# GNSS_SUPPORT.net
KiCad netlist of a schematic drawn in Altium Designer
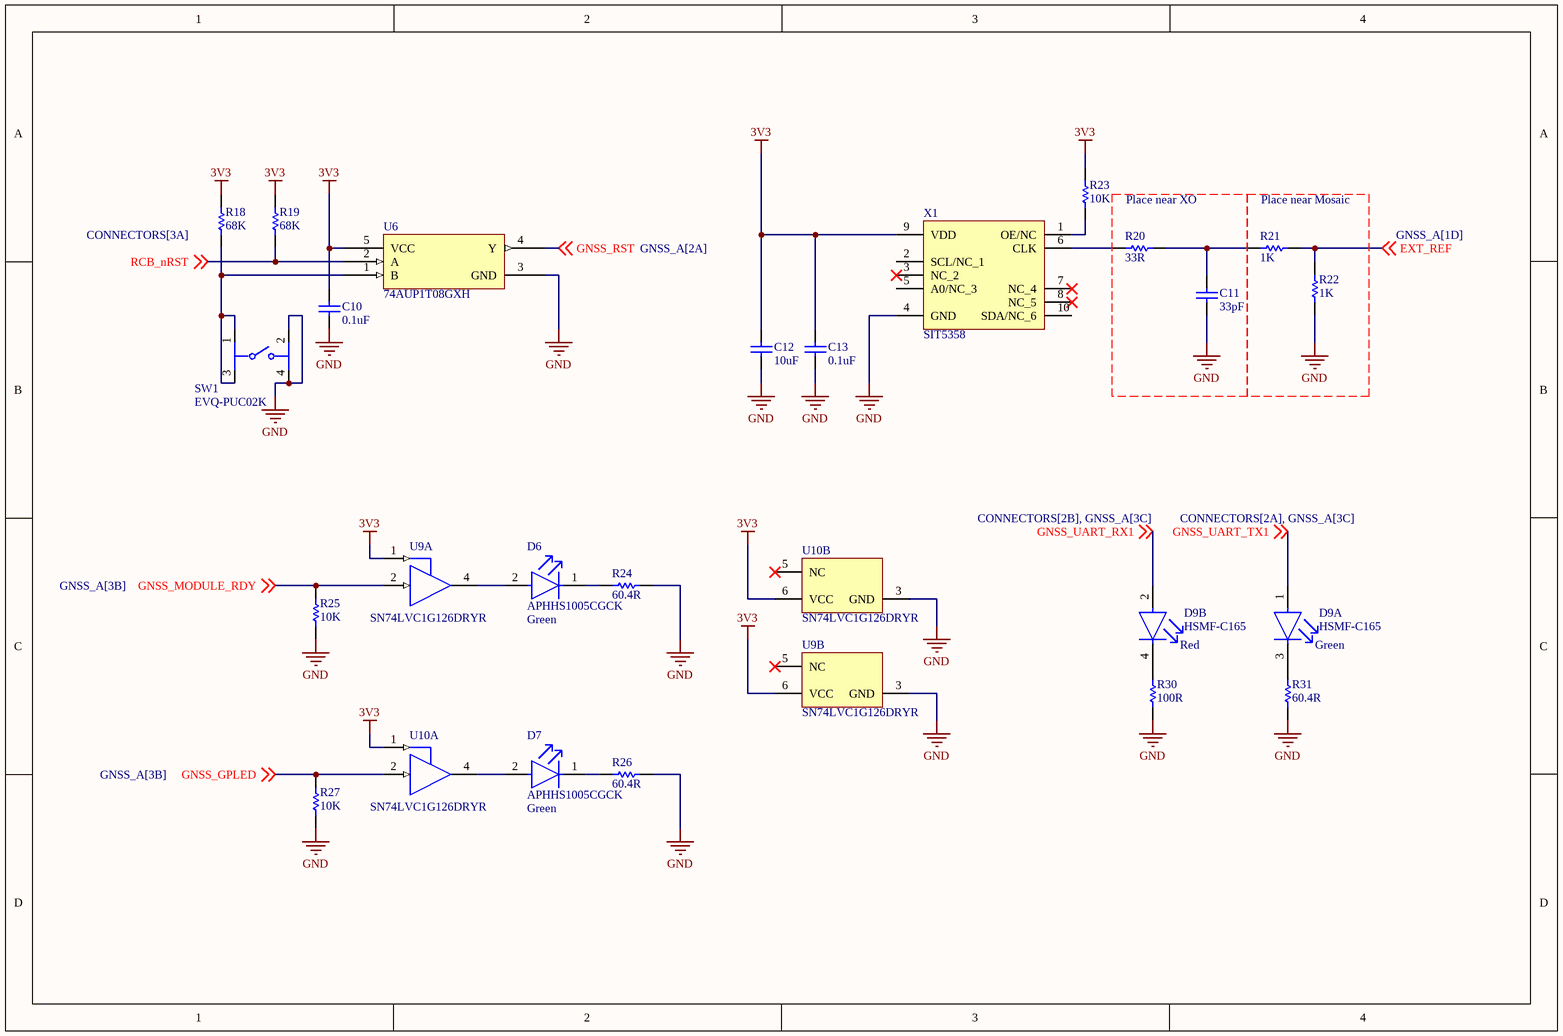
[diagram p0: GNSS_SUPPORT.SchDoc]

(export (version "E")
  (design (tool "Eeschema 10.0.6"))
  (components
    (comp (ref "C10")
      (value "0.1uF")
      (footprint "CAPC1005X56X25LL10T15")
      (fields
        (field (name "MANUFACTURER") "AVX Interconnect / Elco")
        (field (name "PART NUMBER") "04026D104KAT2A")
      )
      (libsource (lib "Altium Content Vault") (part "CAP"))
    )
    (comp (ref "C11")
      (value "33pF")
      (footprint "CAPC1005X55X25ML05T10")
      (fields (field (name "PART NUMBER") "GRM1555C1H330JZ01D") (field (name "MANUFACTURER") "Murata"))
      (libsource (lib "Altium Content Vault") (part "CAP"))
    )
    (comp (ref "C12")
      (value "10uF")
      (footprint "CAPC1005X70X10LL05")
      (description "Chip Capacitor, 10 uF, +/- 20%, -55 to 85 degC, 0402 (1005 Metric), RoHS, Tape and Reel")
      (fields
        (field (name "PCN PART NUMBER") "MLCCPartNumberChange30/Nov/2012")
        (field (name "TOLERANCE") "±20%")
      )
      (libsource (lib "Altium Content Vault") (part "CAP-NP-2"))
    )
    (comp (ref "C13")
      (value "0.1uF")
      (footprint "CAPC1005X56X25LL10T15")
      (fields
        (field (name "MANUFACTURER") "AVX Interconnect / Elco")
        (field (name "PART NUMBER") "04026D104KAT2A")
      )
      (libsource (lib "Altium Content Vault") (part "CAP"))
    )
    (comp (ref "D6")
      (value "APHHS1005CGCK")
      (footprint "FP-APHHS1005CGCK-MFG")
      (description "LED GREEN CLEAR CHIP SMD")
      (fields (field (name "COLOR") "Green"))
      (libsource (lib "Altium Content Vault") (part "8706943c75ba83719d021d2fdc84c58"))
    )
    (comp (ref "D7")
      (value "APHHS1005CGCK")
      (footprint "FP-APHHS1005CGCK-MFG")
      (description "LED GREEN CLEAR CHIP SMD")
      (fields (field (name "COLOR") "Green"))
      (libsource (lib "Altium Content Vault") (part "8706943c75ba83719d021d2fdc84c58"))
    )
    (comp (ref "D9")
      (value "HSMF-C165")
      (footprint "FP-HSMF-C165-MFG")
      (description "LED GREEN/RED DIFFUSED 0603 SMD")
      (libsource (lib "Altium Content Vault") (part "7c1fe340d8ce6b5db8c50b7ec3493de"))
    )
    (comp (ref "R18")
      (value "68K")
      (footprint "RESC1005X40X25LL10T10")
      (fields (field (name "PART NUMBER") "ERA2AEB683X") (field (name "MANUFACTURER") "Panasonic"))
      (libsource (lib "Altium Content Vault") (part "RES"))
    )
    (comp (ref "R19")
      (value "68K")
      (footprint "RESC1005X40X25LL10T10")
      (fields (field (name "PART NUMBER") "ERA2AEB683X") (field (name "MANUFACTURER") "Panasonic"))
      (libsource (lib "Altium Content Vault") (part "RES"))
    )
    (comp (ref "R20")
      (value "33R")
      (footprint "RESC1005X40X25LL05T10")
      (fields (field (name "PART NUMBER") "RC0402FR-0733RL") (field (name "MANUFACTURER") "Yageo / Phycomp"))
      (libsource (lib "Altium Content Vault") (part "RES"))
    )
    (comp (ref "R21")
      (value "1K")
      (footprint "RESC1005X40X25LL05T10")
      (fields (field (name "PART NUMBER") "CRCW04021K00FKEDHP") (field (name "MANUFACTURER") "Vishay Dale"))
      (libsource (lib "Altium Content Vault") (part "RES"))
    )
    (comp (ref "R22")
      (value "1K")
      (footprint "RESC1005X40X25LL05T10")
      (fields (field (name "PART NUMBER") "CRCW04021K00FKEDHP") (field (name "MANUFACTURER") "Vishay Dale"))
      (libsource (lib "Altium Content Vault") (part "RES"))
    )
    (comp (ref "R23")
      (value "10K")
      (footprint "RESC1005X40X25ML05T10")
      (fields (field (name "PART NUMBER") "CRCW040210K0FKEDHP") (field (name "MANUFACTURER") "Vishay Dale"))
      (libsource (lib "Altium Content Vault") (part "RES"))
    )
    (comp (ref "R24")
      (value "60.4R")
      (footprint "RESC1005X40X25ML05T05")
      (fields (field (name "PART NUMBER") "ERJ-2RKF6040X") (field (name "MANUFACTURER") "Panasonic"))
      (libsource (lib "Altium Content Vault") (part "RES"))
    )
    (comp (ref "R25")
      (value "10K")
      (footprint "RESC1005X40X25ML05T10")
      (fields (field (name "PART NUMBER") "CRCW040210K0FKEDHP") (field (name "MANUFACTURER") "Vishay Dale"))
      (libsource (lib "Altium Content Vault") (part "RES"))
    )
    (comp (ref "R26")
      (value "60.4R")
      (footprint "RESC1005X40X25ML05T05")
      (fields (field (name "PART NUMBER") "ERJ-2RKF6040X") (field (name "MANUFACTURER") "Panasonic"))
      (libsource (lib "Altium Content Vault") (part "RES"))
    )
    (comp (ref "R27")
      (value "10K")
      (footprint "RESC1005X40X25ML05T10")
      (fields (field (name "PART NUMBER") "CRCW040210K0FKEDHP") (field (name "MANUFACTURER") "Vishay Dale"))
      (libsource (lib "Altium Content Vault") (part "RES"))
    )
    (comp (ref "R30")
      (value "100R")
      (footprint "RESC1005X40X25LL05T05")
      (description "Chip Resistor, 100 Ohm, +/- 1%, 100 mW, -55 to 155 degC, 0402 (1005 Metric), RoHS, Tape and Reel")
      (fields (field (name "MANUFACTURER") "Basic Passives") (field (name "TOLERANCE") "1%"))
      (libsource (lib "Altium Content Vault") (part "RES-2"))
    )
    (comp (ref "R31")
      (value "60.4R")
      (footprint "RESC1005X40X25ML05T05")
      (fields (field (name "PART NUMBER") "ERJ-2RKF6040X") (field (name "MANUFACTURER") "Panasonic"))
      (libsource (lib "Altium Content Vault") (part "RES"))
    )
    (comp (ref "SW1")
      (value "EVQ-PUC02K")
      (footprint "FP-EVQ-PUC02K-MFG")
      (description "SWITCH TACTILE SPST-NO 0.05A 12V")
      (libsource (lib "Altium Content Vault") (part "cb67941ecbda1860b707deecc235d4d"))
    )
    (comp (ref "U6")
      (value "74AUP1T08GXH")
      (footprint "X2SON5_SOT1226_NEX")
      (description "No Description Available")
      (fields (field (name "COPYRIGHT") "Copyright (C) 2023 Ultra Librarian. All rights reserved."))
      (libsource (lib "74AUP1T08GXH") (part "74AUP1T08GXH"))
    )
    (comp (ref "U9")
      (value "SN74LVC1G126DRYR")
      (footprint "DRY0006A_V")
      (description "Single Bus Buffer Gate With 3-State Outputs, DRY0006A, LARGE T&R")
      (fields
        (field (name "MANUFACTURER") "Texas Instruments")
        (field (name "GENERIC PART NUMBER") "SN74LVC1G126")
      )
      (libsource (lib "Altium Content Vault") (part "TI-SN74XXX1G126-6"))
    )
    (comp (ref "U10")
      (value "SN74LVC1G126DRYR")
      (footprint "DRY0006A_V")
      (description "Single Bus Buffer Gate With 3-State Outputs, DRY0006A, LARGE T&R")
      (fields
        (field (name "MANUFACTURER") "Texas Instruments")
        (field (name "GENERIC PART NUMBER") "SN74LVC1G126")
      )
      (libsource (lib "Altium Content Vault") (part "TI-SN74XXX1G126-6"))
    )
    (comp (ref "X1")
      (value "SIT5358")
      (footprint "SIT5358")
      (description "1 to 60 MHz, ±50 ppb Super-TCXO")
      (fields (field (name "MANUFACTURER_PART_NUMBER") "SIT5358AN-FR-33N0-10.000000"))
      (libsource (lib "SIT5358") (part "SIT5358"))
    )
  )
  (nets
    (net (code "1") (name "3V3") (class "Default")
      (node (ref "C10") (pin "2") (pinfunction "2_2") (pintype "passive"))
      (node (ref "C12") (pin "2") (pinfunction "2_2") (pintype "passive"))
      (node (ref "C13") (pin "2") (pinfunction "2_2") (pintype "passive"))
      (node (ref "R18") (pin "2") (pinfunction "2_2") (pintype "passive"))
      (node (ref "R19") (pin "2") (pinfunction "2_2") (pintype "passive"))
      (node (ref "R23") (pin "2") (pinfunction "2_2") (pintype "passive"))
      (node (ref "U10") (pin "1") (pinfunction "OE_1") (pintype "input"))
      (node (ref "U10") (pin "6") (pinfunction "VCC_6") (pintype "power_in"))
      (node (ref "U6") (pin "5") (pinfunction "VCC_5") (pintype "power_in"))
      (node (ref "U9") (pin "1") (pinfunction "OE_1") (pintype "input"))
      (node (ref "U9") (pin "6") (pinfunction "VCC_6") (pintype "power_in"))
      (node (ref "X1") (pin "9") (pinfunction "VDD_9") (pintype "passive"))
    )
    (net (code "2") (name "EXT_REF") (class "Default")
      (node (ref "R21") (pin "2") (pinfunction "2_2") (pintype "passive"))
      (node (ref "R22") (pin "2") (pinfunction "2_2") (pintype "passive"))
    )
    (net (code "3") (name "GND") (class "Default")
      (node (ref "C10") (pin "1") (pinfunction "1_1") (pintype "passive"))
      (node (ref "C11") (pin "1") (pinfunction "1_1") (pintype "passive"))
      (node (ref "C12") (pin "1") (pinfunction "1_1") (pintype "passive"))
      (node (ref "C13") (pin "1") (pinfunction "1_1") (pintype "passive"))
      (node (ref "R22") (pin "1") (pinfunction "1_1") (pintype "passive"))
      (node (ref "R24") (pin "1") (pinfunction "1_1") (pintype "passive"))
      (node (ref "R25") (pin "1") (pinfunction "1_1") (pintype "passive"))
      (node (ref "R26") (pin "1") (pinfunction "1_1") (pintype "passive"))
      (node (ref "R27") (pin "1") (pinfunction "1_1") (pintype "passive"))
      (node (ref "R30") (pin "1") (pinfunction "1_1") (pintype "passive"))
      (node (ref "R31") (pin "2") (pinfunction "2_2") (pintype "passive"))
      (node (ref "SW1") (pin "2") (pinfunction "2_2") (pintype "passive"))
      (node (ref "SW1") (pin "4") (pinfunction "4_4") (pintype "passive"))
      (node (ref "U10") (pin "3") (pinfunction "GND_3") (pintype "power_in"))
      (node (ref "U6") (pin "3") (pinfunction "GND_3") (pintype "passive"))
      (node (ref "U9") (pin "3") (pinfunction "GND_3") (pintype "power_in"))
      (node (ref "X1") (pin "4") (pinfunction "GND_4") (pintype "passive"))
    )
    (net (code "4") (name "GNSS_GPLED") (class "Default")
      (node (ref "R27") (pin "2") (pinfunction "2_2") (pintype "passive"))
      (node (ref "U10") (pin "2") (pinfunction "A_2") (pintype "input"))
    )
    (net (code "5") (name "GNSS_MODULE_RDY") (class "Default")
      (node (ref "R25") (pin "2") (pinfunction "2_2") (pintype "passive"))
      (node (ref "U9") (pin "2") (pinfunction "A_2") (pintype "input"))
    )
    (net (code "6") (name "GNSS_RST") (class "Default")
      (node (ref "U6") (pin "4") (pinfunction "Y_4") (pintype "output"))
    )
    (net (code "7") (name "GNSS_UART_RX1") (class "Default")
      (node (ref "D9") (pin "2") (pinfunction "RED_A_2") (pintype "passive"))
    )
    (net (code "8") (name "GNSS_UART_TX1") (class "Default")
      (node (ref "D9") (pin "1") (pinfunction "GREEN_A_1") (pintype "passive"))
    )
    (net (code "9") (name "Net-(C11-Pad2)") (class "Default")
      (node (ref "C11") (pin "2") (pinfunction "2_2") (pintype "passive"))
      (node (ref "R20") (pin "2") (pinfunction "2_2") (pintype "passive"))
      (node (ref "R21") (pin "1") (pinfunction "1_1") (pintype "passive"))
    )
    (net (code "10") (name "Net-(D6-A)") (class "Default")
      (node (ref "D6") (pin "2") (pinfunction "A_2") (pintype "passive"))
      (node (ref "U9") (pin "4") (pinfunction "Y_4") (pintype "tri_state"))
    )
    (net (code "11") (name "Net-(D6-C)") (class "Default")
      (node (ref "D6") (pin "1") (pinfunction "C_1") (pintype "passive"))
      (node (ref "R24") (pin "2") (pinfunction "2_2") (pintype "passive"))
    )
    (net (code "12") (name "Net-(D7-A)") (class "Default")
      (node (ref "D7") (pin "2") (pinfunction "A_2") (pintype "passive"))
      (node (ref "U10") (pin "4") (pinfunction "Y_4") (pintype "tri_state"))
    )
    (net (code "13") (name "Net-(D7-C)") (class "Default")
      (node (ref "D7") (pin "1") (pinfunction "C_1") (pintype "passive"))
      (node (ref "R26") (pin "2") (pinfunction "2_2") (pintype "passive"))
    )
    (net (code "14") (name "Net-(D9A-GREEN_C)") (class "Default")
      (node (ref "D9") (pin "3") (pinfunction "GREEN_C_3") (pintype "passive"))
      (node (ref "R31") (pin "1") (pinfunction "1_1") (pintype "passive"))
    )
    (net (code "15") (name "Net-(D9B-RED_C)") (class "Default")
      (node (ref "D9") (pin "4") (pinfunction "RED_C_4") (pintype "passive"))
      (node (ref "R30") (pin "2") (pinfunction "2_2") (pintype "passive"))
    )
    (net (code "16") (name "Net-(U6-B)") (class "Default")
      (node (ref "R18") (pin "1") (pinfunction "1_1") (pintype "passive"))
      (node (ref "SW1") (pin "1") (pinfunction "1_1") (pintype "passive"))
      (node (ref "SW1") (pin "3") (pinfunction "3_3") (pintype "passive"))
      (node (ref "U6") (pin "1") (pinfunction "B_1") (pintype "input"))
    )
    (net (code "17") (name "Net-(X1-CLK)") (class "Default")
      (node (ref "R20") (pin "1") (pinfunction "1_1") (pintype "passive"))
      (node (ref "X1") (pin "6") (pinfunction "CLK_6") (pintype "passive"))
    )
    (net (code "18") (name "Net-(X1-OE{slash}NC)") (class "Default")
      (node (ref "R23") (pin "1") (pinfunction "1_1") (pintype "passive"))
      (node (ref "X1") (pin "1") (pinfunction "OE/NC_1") (pintype "passive"))
    )
    (net (code "19") (name "RCB_nRST") (class "Default")
      (node (ref "R19") (pin "1") (pinfunction "1_1") (pintype "passive"))
      (node (ref "U6") (pin "2") (pinfunction "A_2") (pintype "input"))
    )
    (net (code "20") (name "unconnected-(U9B-NC-Pad5)") (class "Default")
      (node (ref "U9") (pin "5") (pinfunction "NC_5") (pintype "passive+no_connect"))
    )
    (net (code "21") (name "unconnected-(U10B-NC-Pad5)") (class "Default")
      (node (ref "U10") (pin "5") (pinfunction "NC_5") (pintype "passive+no_connect"))
    )
    (net (code "22") (name "unconnected-(X1-A0{slash}NC_3-Pad5)") (class "Default")
      (node (ref "X1") (pin "5") (pinfunction "A0/NC_3_5") (pintype "passive"))
    )
    (net (code "23") (name "unconnected-(X1-NC_2-Pad3)") (class "Default")
      (node (ref "X1") (pin "3") (pinfunction "NC_2_3") (pintype "passive+no_connect"))
    )
    (net (code "24") (name "unconnected-(X1-NC_4-Pad7)") (class "Default")
      (node (ref "X1") (pin "7") (pinfunction "NC_4_7") (pintype "passive+no_connect"))
    )
    (net (code "25") (name "unconnected-(X1-NC_5-Pad8)") (class "Default")
      (node (ref "X1") (pin "8") (pinfunction "NC_5_8") (pintype "passive+no_connect"))
    )
    (net (code "26") (name "unconnected-(X1-SCL{slash}NC_1-Pad2)") (class "Default")
      (node (ref "X1") (pin "2") (pinfunction "SCL/NC_1_2") (pintype "passive"))
    )
    (net (code "27") (name "unconnected-(X1-SDA{slash}NC_6-Pad10)") (class "Default")
      (node (ref "X1") (pin "10") (pinfunction "SDA/NC_6_10") (pintype "passive"))
    )
  )
)
